# Relay_output_driver_modul_4ch.net
KiCad netlist of a schematic drawn in EAGLE
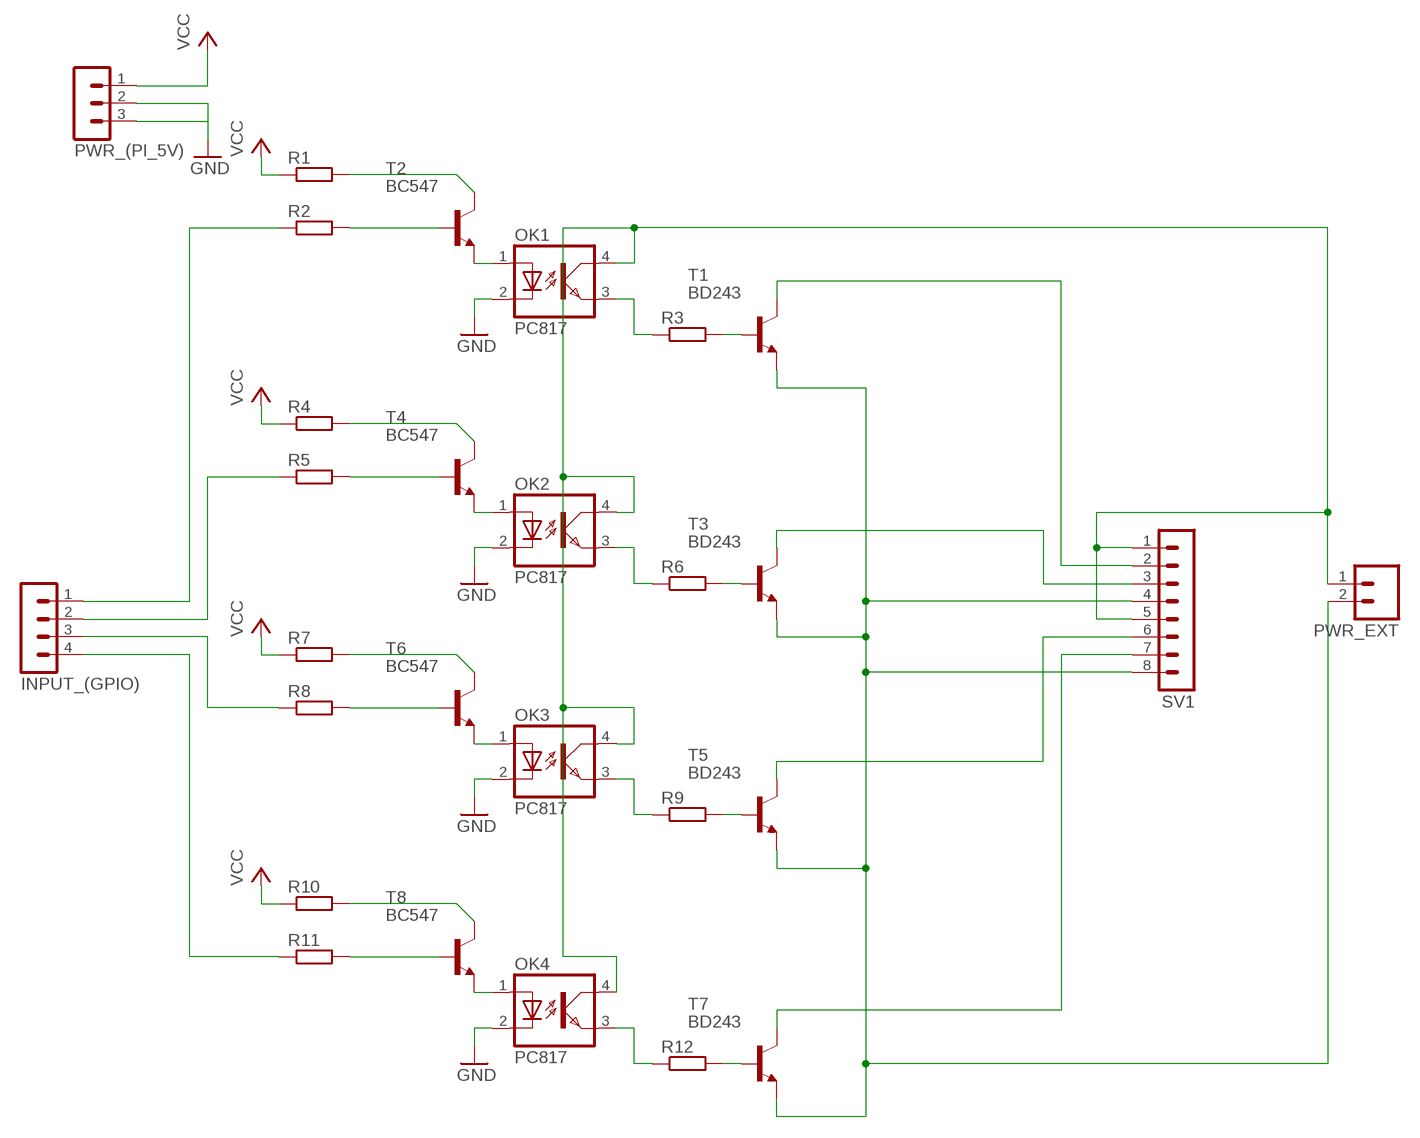
[diagram p0: schematic, sheet 1]

(export (version "E")
  (design (tool "Eeschema 10.0.6"))
  (components
    (comp (ref "INPUT_(GPIO)")
      (value "MA04-1")
      (footprint "eagle-import:MA04-1")
      (libsource (lib "eagle-import") (part "MA04-1"))
    )
    (comp (ref "OK1")
      (value "PC817")
      (footprint "eagle-import:DIL04")
      (fields (field (name "MPN") "PC817X4J000F"))
      (libsource (lib "eagle-import") (part "PC817"))
    )
    (comp (ref "OK2")
      (value "PC817")
      (footprint "eagle-import:DIL04")
      (fields (field (name "MPN") "PC817X4J000F"))
      (libsource (lib "eagle-import") (part "PC817"))
    )
    (comp (ref "OK3")
      (value "PC817")
      (footprint "eagle-import:DIL04")
      (fields (field (name "MPN") "PC817X4J000F"))
      (libsource (lib "eagle-import") (part "PC817"))
    )
    (comp (ref "OK4")
      (value "PC817")
      (footprint "eagle-import:DIL04")
      (fields (field (name "MPN") "PC817X4J000F"))
      (libsource (lib "eagle-import") (part "PC817"))
    )
    (comp (ref "PWR_(PI_5V)")
      (value "MA03-1")
      (footprint "eagle-import:MA03-1")
      (libsource (lib "eagle-import") (part "MA03-1"))
    )
    (comp (ref "PWR_EXT")
      (value "MA02")
      (footprint "eagle-import:02PA")
      (libsource (lib "eagle-import") (part "MA02"))
    )
    (comp (ref "R1")
      (value "R-EU_0207/10")
      (footprint "eagle-import:0207_10")
      (libsource (lib "eagle-import") (part "R-EU_0207/10"))
    )
    (comp (ref "R2")
      (value "R-EU_0207/10")
      (footprint "eagle-import:0207_10")
      (libsource (lib "eagle-import") (part "R-EU_0207/10"))
    )
    (comp (ref "R3")
      (value "R-EU_0207/10")
      (footprint "eagle-import:0207_10")
      (libsource (lib "eagle-import") (part "R-EU_0207/10"))
    )
    (comp (ref "R4")
      (value "R-EU_0207/10")
      (footprint "eagle-import:0207_10")
      (libsource (lib "eagle-import") (part "R-EU_0207/10"))
    )
    (comp (ref "R5")
      (value "R-EU_0207/10")
      (footprint "eagle-import:0207_10")
      (libsource (lib "eagle-import") (part "R-EU_0207/10"))
    )
    (comp (ref "R6")
      (value "R-EU_0207/10")
      (footprint "eagle-import:0207_10")
      (libsource (lib "eagle-import") (part "R-EU_0207/10"))
    )
    (comp (ref "R7")
      (value "R-EU_0207/10")
      (footprint "eagle-import:0207_10")
      (libsource (lib "eagle-import") (part "R-EU_0207/10"))
    )
    (comp (ref "R8")
      (value "R-EU_0207/10")
      (footprint "eagle-import:0207_10")
      (libsource (lib "eagle-import") (part "R-EU_0207/10"))
    )
    (comp (ref "R9")
      (value "R-EU_0207/10")
      (footprint "eagle-import:0207_10")
      (libsource (lib "eagle-import") (part "R-EU_0207/10"))
    )
    (comp (ref "R10")
      (value "R-EU_0207/10")
      (footprint "eagle-import:0207_10")
      (libsource (lib "eagle-import") (part "R-EU_0207/10"))
    )
    (comp (ref "R11")
      (value "R-EU_0207/10")
      (footprint "eagle-import:0207_10")
      (libsource (lib "eagle-import") (part "R-EU_0207/10"))
    )
    (comp (ref "R12")
      (value "R-EU_0207/10")
      (footprint "eagle-import:0207_10")
      (libsource (lib "eagle-import") (part "R-EU_0207/10"))
    )
    (comp (ref "SV1")
      (value "MA08-1")
      (footprint "eagle-import:MA08-1")
      (libsource (lib "eagle-import") (part "MA08-1"))
    )
    (comp (ref "T1")
      (value "BD243")
      (footprint "eagle-import:TO220")
      (libsource (lib "eagle-import") (part "BD243"))
    )
    (comp (ref "T2")
      (value "BC547")
      (footprint "eagle-import:TO92")
      (libsource (lib "eagle-import") (part "BC547"))
    )
    (comp (ref "T3")
      (value "BD243")
      (footprint "eagle-import:TO220")
      (libsource (lib "eagle-import") (part "BD243"))
    )
    (comp (ref "T4")
      (value "BC547")
      (footprint "eagle-import:TO92")
      (libsource (lib "eagle-import") (part "BC547"))
    )
    (comp (ref "T5")
      (value "BD243")
      (footprint "eagle-import:TO220")
      (libsource (lib "eagle-import") (part "BD243"))
    )
    (comp (ref "T6")
      (value "BC547")
      (footprint "eagle-import:TO92")
      (libsource (lib "eagle-import") (part "BC547"))
    )
    (comp (ref "T7")
      (value "BD243")
      (footprint "eagle-import:TO220")
      (libsource (lib "eagle-import") (part "BD243"))
    )
    (comp (ref "T8")
      (value "BC547")
      (footprint "eagle-import:TO92")
      (libsource (lib "eagle-import") (part "BC547"))
    )
  )
  (nets
    (net (code "1") (name "GND") (class "Default")
      (node (ref "OK1") (pin "2") (pinfunction "C_2") (pintype "passive"))
      (node (ref "OK2") (pin "2") (pinfunction "C_2") (pintype "passive"))
      (node (ref "OK3") (pin "2") (pinfunction "C_2") (pintype "passive"))
      (node (ref "OK4") (pin "2") (pinfunction "C_2") (pintype "passive"))
      (node (ref "PWR_(PI_5V)") (pin "2") (pinfunction "2_2") (pintype "passive"))
      (node (ref "PWR_(PI_5V)") (pin "3") (pinfunction "3_3") (pintype "passive"))
    )
    (net (code "2") (name "Net-(INPUT_(GPIO)-Pad1)") (class "Default")
      (node (ref "INPUT_(GPIO)") (pin "1") (pinfunction "1_1") (pintype "passive"))
      (node (ref "R2") (pin "1") (pinfunction "1_1") (pintype "passive"))
    )
    (net (code "3") (name "Net-(INPUT_(GPIO)-Pad2)") (class "Default")
      (node (ref "INPUT_(GPIO)") (pin "2") (pinfunction "2_2") (pintype "passive"))
      (node (ref "R5") (pin "1") (pinfunction "1_1") (pintype "passive"))
    )
    (net (code "4") (name "Net-(INPUT_(GPIO)-Pad3)") (class "Default")
      (node (ref "INPUT_(GPIO)") (pin "3") (pinfunction "3_3") (pintype "passive"))
      (node (ref "R8") (pin "1") (pinfunction "1_1") (pintype "passive"))
    )
    (net (code "5") (name "Net-(INPUT_(GPIO)-Pad4)") (class "Default")
      (node (ref "INPUT_(GPIO)") (pin "4") (pinfunction "4_4") (pintype "passive"))
      (node (ref "R11") (pin "1") (pinfunction "1_1") (pintype "passive"))
    )
    (net (code "6") (name "Net-(OK1-A)") (class "Default")
      (node (ref "OK1") (pin "1") (pinfunction "A_1") (pintype "passive"))
      (node (ref "T2") (pin "1") (pinfunction "E_1") (pintype "passive"))
    )
    (net (code "7") (name "Net-(OK1-COL)") (class "Default")
      (node (ref "OK1") (pin "4") (pinfunction "COL_4") (pintype "passive"))
      (node (ref "OK2") (pin "4") (pinfunction "COL_4") (pintype "passive"))
      (node (ref "OK3") (pin "4") (pinfunction "COL_4") (pintype "passive"))
      (node (ref "OK4") (pin "4") (pinfunction "COL_4") (pintype "passive"))
      (node (ref "PWR_EXT") (pin "1") (pinfunction "1_1") (pintype "passive"))
      (node (ref "SV1") (pin "1") (pinfunction "1_1") (pintype "passive"))
      (node (ref "SV1") (pin "5") (pinfunction "5_5") (pintype "passive"))
    )
    (net (code "8") (name "Net-(OK1-EMIT)") (class "Default")
      (node (ref "OK1") (pin "3") (pinfunction "EMIT_3") (pintype "passive"))
      (node (ref "R3") (pin "1") (pinfunction "1_1") (pintype "passive"))
    )
    (net (code "9") (name "Net-(OK2-A)") (class "Default")
      (node (ref "OK2") (pin "1") (pinfunction "A_1") (pintype "passive"))
      (node (ref "T4") (pin "1") (pinfunction "E_1") (pintype "passive"))
    )
    (net (code "10") (name "Net-(OK2-EMIT)") (class "Default")
      (node (ref "OK2") (pin "3") (pinfunction "EMIT_3") (pintype "passive"))
      (node (ref "R6") (pin "1") (pinfunction "1_1") (pintype "passive"))
    )
    (net (code "11") (name "Net-(OK3-A)") (class "Default")
      (node (ref "OK3") (pin "1") (pinfunction "A_1") (pintype "passive"))
      (node (ref "T6") (pin "1") (pinfunction "E_1") (pintype "passive"))
    )
    (net (code "12") (name "Net-(OK3-EMIT)") (class "Default")
      (node (ref "OK3") (pin "3") (pinfunction "EMIT_3") (pintype "passive"))
      (node (ref "R9") (pin "1") (pinfunction "1_1") (pintype "passive"))
    )
    (net (code "13") (name "Net-(OK4-A)") (class "Default")
      (node (ref "OK4") (pin "1") (pinfunction "A_1") (pintype "passive"))
      (node (ref "T8") (pin "1") (pinfunction "E_1") (pintype "passive"))
    )
    (net (code "14") (name "Net-(OK4-EMIT)") (class "Default")
      (node (ref "OK4") (pin "3") (pinfunction "EMIT_3") (pintype "passive"))
      (node (ref "R12") (pin "1") (pinfunction "1_1") (pintype "passive"))
    )
    (net (code "15") (name "Net-(T1-B)") (class "Default")
      (node (ref "R3") (pin "2") (pinfunction "2_2") (pintype "passive"))
      (node (ref "T1") (pin "1") (pinfunction "B_1") (pintype "passive"))
    )
    (net (code "16") (name "Net-(T1-C)") (class "Default")
      (node (ref "SV1") (pin "2") (pinfunction "2_2") (pintype "passive"))
      (node (ref "T1") (pin "2") (pinfunction "C_2") (pintype "passive"))
    )
    (net (code "17") (name "Net-(T1-E)") (class "Default")
      (node (ref "PWR_EXT") (pin "2") (pinfunction "2_2") (pintype "passive"))
      (node (ref "SV1") (pin "4") (pinfunction "4_4") (pintype "passive"))
      (node (ref "SV1") (pin "8") (pinfunction "8_8") (pintype "passive"))
      (node (ref "T1") (pin "3") (pinfunction "E_3") (pintype "passive"))
      (node (ref "T3") (pin "3") (pinfunction "E_3") (pintype "passive"))
      (node (ref "T5") (pin "3") (pinfunction "E_3") (pintype "passive"))
      (node (ref "T7") (pin "3") (pinfunction "E_3") (pintype "passive"))
    )
    (net (code "18") (name "Net-(T2-B)") (class "Default")
      (node (ref "R2") (pin "2") (pinfunction "2_2") (pintype "passive"))
      (node (ref "T2") (pin "2") (pinfunction "B_2") (pintype "passive"))
    )
    (net (code "19") (name "Net-(T2-C)") (class "Default")
      (node (ref "R1") (pin "2") (pinfunction "2_2") (pintype "passive"))
      (node (ref "T2") (pin "3") (pinfunction "C_3") (pintype "passive"))
    )
    (net (code "20") (name "Net-(T3-B)") (class "Default")
      (node (ref "R6") (pin "2") (pinfunction "2_2") (pintype "passive"))
      (node (ref "T3") (pin "1") (pinfunction "B_1") (pintype "passive"))
    )
    (net (code "21") (name "Net-(T3-C)") (class "Default")
      (node (ref "SV1") (pin "3") (pinfunction "3_3") (pintype "passive"))
      (node (ref "T3") (pin "2") (pinfunction "C_2") (pintype "passive"))
    )
    (net (code "22") (name "Net-(T4-B)") (class "Default")
      (node (ref "R5") (pin "2") (pinfunction "2_2") (pintype "passive"))
      (node (ref "T4") (pin "2") (pinfunction "B_2") (pintype "passive"))
    )
    (net (code "23") (name "Net-(T4-C)") (class "Default")
      (node (ref "R4") (pin "2") (pinfunction "2_2") (pintype "passive"))
      (node (ref "T4") (pin "3") (pinfunction "C_3") (pintype "passive"))
    )
    (net (code "24") (name "Net-(T5-B)") (class "Default")
      (node (ref "R9") (pin "2") (pinfunction "2_2") (pintype "passive"))
      (node (ref "T5") (pin "1") (pinfunction "B_1") (pintype "passive"))
    )
    (net (code "25") (name "Net-(T5-C)") (class "Default")
      (node (ref "SV1") (pin "6") (pinfunction "6_6") (pintype "passive"))
      (node (ref "T5") (pin "2") (pinfunction "C_2") (pintype "passive"))
    )
    (net (code "26") (name "Net-(T6-B)") (class "Default")
      (node (ref "R8") (pin "2") (pinfunction "2_2") (pintype "passive"))
      (node (ref "T6") (pin "2") (pinfunction "B_2") (pintype "passive"))
    )
    (net (code "27") (name "Net-(T6-C)") (class "Default")
      (node (ref "R7") (pin "2") (pinfunction "2_2") (pintype "passive"))
      (node (ref "T6") (pin "3") (pinfunction "C_3") (pintype "passive"))
    )
    (net (code "28") (name "Net-(T7-B)") (class "Default")
      (node (ref "R12") (pin "2") (pinfunction "2_2") (pintype "passive"))
      (node (ref "T7") (pin "1") (pinfunction "B_1") (pintype "passive"))
    )
    (net (code "29") (name "Net-(T7-C)") (class "Default")
      (node (ref "SV1") (pin "7") (pinfunction "7_7") (pintype "passive"))
      (node (ref "T7") (pin "2") (pinfunction "C_2") (pintype "passive"))
    )
    (net (code "30") (name "Net-(T8-B)") (class "Default")
      (node (ref "R11") (pin "2") (pinfunction "2_2") (pintype "passive"))
      (node (ref "T8") (pin "2") (pinfunction "B_2") (pintype "passive"))
    )
    (net (code "31") (name "Net-(T8-C)") (class "Default")
      (node (ref "R10") (pin "2") (pinfunction "2_2") (pintype "passive"))
      (node (ref "T8") (pin "3") (pinfunction "C_3") (pintype "passive"))
    )
    (net (code "32") (name "VCC") (class "Default")
      (node (ref "PWR_(PI_5V)") (pin "1") (pinfunction "1_1") (pintype "passive"))
      (node (ref "R1") (pin "1") (pinfunction "1_1") (pintype "passive"))
      (node (ref "R10") (pin "1") (pinfunction "1_1") (pintype "passive"))
      (node (ref "R4") (pin "1") (pinfunction "1_1") (pintype "passive"))
      (node (ref "R7") (pin "1") (pinfunction "1_1") (pintype "passive"))
    )
  )
)
